# schematic.net
KiCad netlist of a schematic drawn in Altium Designer
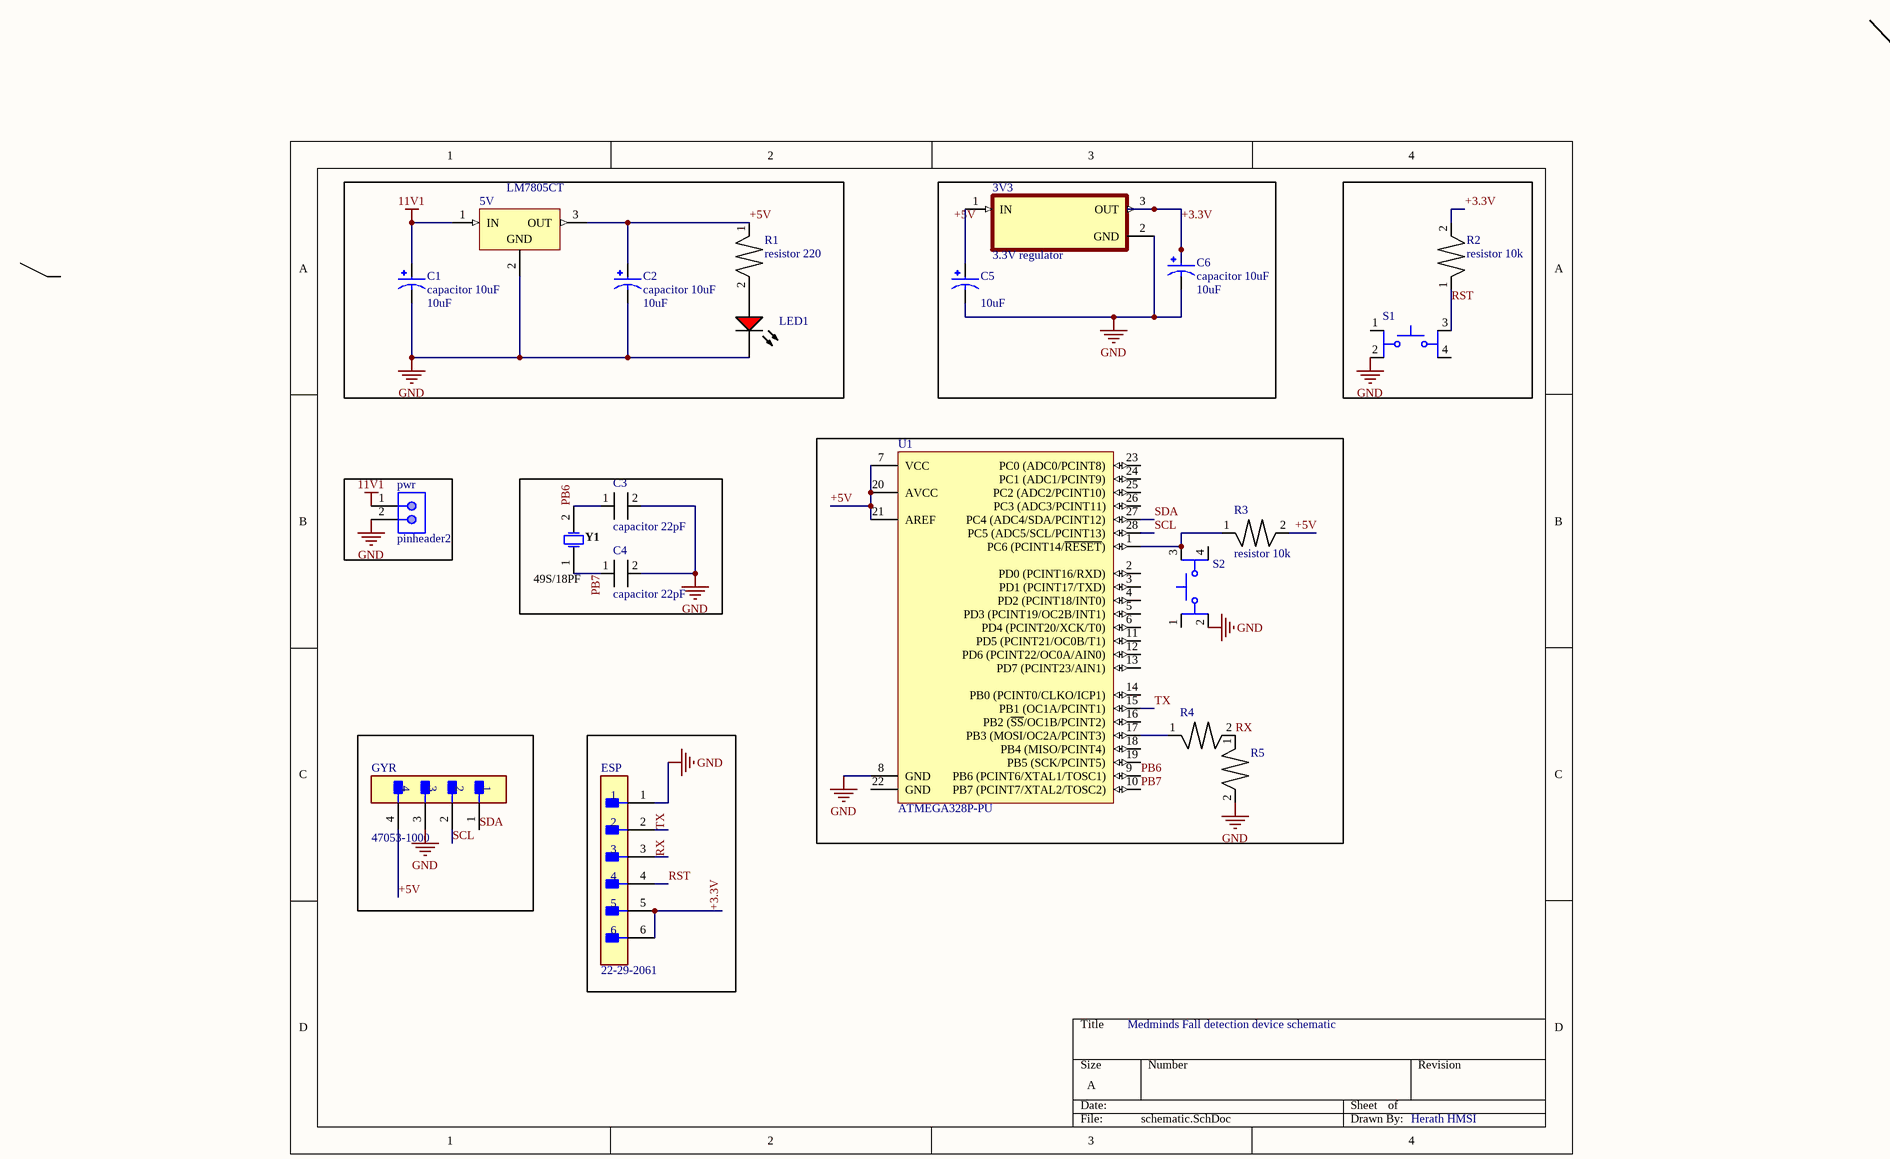
[diagram p0: schematic.SchDoc]

(export (version "E")
  (design (tool "Eeschema 10.0.6"))
  (components
    (comp (ref "3V3")
      (value "3.3V regulator")
      (footprint "3.3V regulator")
      (libsource (lib "schematiclib") (part "3.3V regulator"))
    )
    (comp (ref "5V")
      (value "LM7805CT")
      (footprint "FAIR-TO-220-3")
      (description "Fixed Positive Standard Regulator, 5VBIPolar, PSFM3")
      (libsource (lib "herathhmsi 21") (part "FAIR-LM7805CT-TO220-3"))
    )
    (comp (ref "C1")
      (value "capacitor 10uF")
      (footprint "Capacitor10uF")
      (fields
        (field (name "MANUFACTURER") "Panasonic")
        (field (name "MANUFACTURER PART NUMBER") "ECA-1HM100I")
        (field (name "ALTIUM_VALUE") "10uF")
      )
      (libsource (lib "schematiclib") (part "ECA-1HM100I (2)"))
    )
    (comp (ref "C2")
      (value "capacitor 10uF")
      (footprint "Capacitor10uF")
      (fields
        (field (name "MANUFACTURER") "Panasonic")
        (field (name "MANUFACTURER PART NUMBER") "ECA-1HM100I")
        (field (name "ALTIUM_VALUE") "10uF")
      )
      (libsource (lib "schematiclib") (part "ECA-1HM100I (2)"))
    )
    (comp (ref "C3")
      (value "capacitor 22pF")
      (footprint "Capacitor - duplicate")
      (fields
        (field (name "MANUFACTURER") "Murata")
        (field (name "MANUFACTURER PART NUMBER") "DE21XSA220KN3AX02F")
      )
      (libsource (lib "schematiclib") (part "DE21XSA220KN3AX02F"))
    )
    (comp (ref "C4")
      (value "capacitor 22pF")
      (footprint "Capacitor - duplicate")
      (fields
        (field (name "MANUFACTURER") "Murata")
        (field (name "MANUFACTURER PART NUMBER") "DE21XSA220KN3AX02F")
      )
      (libsource (lib "schematiclib") (part "DE21XSA220KN3AX02F"))
    )
    (comp (ref "C5")
      (value "10uF")
      (footprint "Capacitor10uF")
      (fields
        (field (name "MANUFACTURER") "Panasonic")
        (field (name "MANUFACTURER PART NUMBER") "ECA-1HM100I")
        (field (name "Comment") "capacitor 10uF")
      )
      (libsource (lib "schematiclib") (part "ECA-1HM100I (2)"))
    )
    (comp (ref "C6")
      (value "capacitor 10uF")
      (footprint "Capacitor10uF")
      (fields
        (field (name "MANUFACTURER") "Panasonic")
        (field (name "MANUFACTURER PART NUMBER") "ECA-1HM100I")
        (field (name "ALTIUM_VALUE") "10uF")
      )
      (libsource (lib "schematiclib") (part "ECA-1HM100I (2)"))
    )
    (comp (ref "ESP")
      (value "22-29-2061")
      (footprint "FP-22-29-2061-MFG")
      (libsource (lib "schematiclib") (part "22-29-2061"))
    )
    (comp (ref "GYR")
      (value "47053-1000")
      (footprint "FP-47053-1000-MFG")
      (description "CONN HEADER VERT 4POS 2.54MM")
      (libsource (lib "Altium Content Vault") (part "299a8cea1bdcbc3624fe62c390fa72c"))
    )
    (comp (ref "LED1")
      (value "LED1")
      (footprint "INDPR60-254-520X380X650")
      (description "LED Uni-Color Red, 100 mW, 30 mA, -55 to 100 degC, 2-Pin THD, RoHS, Bulk")
      (fields (field (name "MANUFACTURER") "Lite-On"))
      (libsource (lib "herathhmsi 21") (part "LED-RED-AK-2"))
    )
    (comp (ref "pwr")
      (value "pinheader2")
      (footprint "TECO-5-146280-2_V")
      (libsource (lib "schematiclib") (part "pinheader2"))
    )
    (comp (ref "R1")
      (value "resistor 220")
      (footprint "Axial 0.4")
      (description "Fixed Resistor, Carbon Film, 0.25W, 220ohm, 350V, 5% +/-Tol, -400,0ppm/Cel, Through Hole Mount")
      (fields
        (field (name "MANUFACTURER") "Stackpole Electronics")
        (field (name "MANUFACTURER PART NUMBER") "CF14JT220R")
      )
      (libsource (lib "schematiclib") (part "CF14JT220R"))
    )
    (comp (ref "R2")
      (value "resistor 10k")
      (footprint "Axial 0.4")
      (description "Fixed Resistor, Carbon Film, 0.25W, 10000ohm, 350V, 5% +/-Tol, -500,0ppm/Cel, Through Hole Mount")
      (fields
        (field (name "MANUFACTURER") "Stackpole Electronics")
        (field (name "MANUFACTURER PART NUMBER") "CF14JT10K0")
      )
      (libsource (lib "schematiclib") (part "CF14JT10K0"))
    )
    (comp (ref "R3")
      (value "resistor 10k")
      (footprint "Axial 0.4")
      (description "Fixed Resistor, Carbon Film, 0.25W, 10000ohm, 350V, 5% +/-Tol, -500,0ppm/Cel, Through Hole Mount")
      (fields
        (field (name "MANUFACTURER") "Stackpole Electronics")
        (field (name "MANUFACTURER PART NUMBER") "CF14JT10K0")
      )
      (libsource (lib "schematiclib") (part "CF14JT10K0"))
    )
    (comp (ref "R4")
      (value "resistor1k")
      (footprint "Axial 0.4")
      (description "Fixed Resistor, Carbon Film, 0.25W, 1000ohm, 350V, 5% +/-Tol, -400,0ppm/Cel, Through Hole Mount")
      (fields
        (field (name "MANUFACTURER") "Stackpole Electronics")
        (field (name "MANUFACTURER PART NUMBER") "CF14JT1K00")
      )
      (libsource (lib "schematiclib") (part "CF14JT1K00"))
    )
    (comp (ref "R5")
      (value "resistor 2k")
      (footprint "Axial 0.4")
      (description "Res Carbon Film 2K Ohm 5% 1/4W -400ppm/°C to 0ppm/°C Conformal AXL Thru-Hole T/R")
      (fields
        (field (name "MANUFACTURER") "Stackpole Electronics")
        (field (name "MANUFACTURER PART NUMBER") "CF14JT2K00")
      )
      (libsource (lib "schematiclib") (part "CF14JT2K00"))
    )
    (comp (ref "S1")
      (value "tacktile switch")
      (footprint "SW_TL1105AF160Q")
      (fields
        (field (name "MANUFACTURER") "E-Switch")
        (field (name "MANUFACTURER PART NUMBER") "TL1105AF160Q")
      )
      (libsource (lib "schematiclib") (part "TL1105AF160Q"))
    )
    (comp (ref "S2")
      (value "tacktile switch")
      (footprint "SW_TL1105AF160Q")
      (fields
        (field (name "MANUFACTURER") "E-Switch")
        (field (name "MANUFACTURER PART NUMBER") "TL1105AF160Q")
      )
      (libsource (lib "") (part "TL1105AF160Q_1"))
    )
    (comp (ref "U1")
      (value "ATMEGA328P-PU")
      (footprint "ATML-28P3")
      (fields (field (name "MANUFACTURER") "Atmel"))
      (libsource (lib "herathhmsi 21") (part "MC-8B-ATM48-IL28"))
    )
    (comp (ref "Y1")
      (value "49S/18PF")
      (footprint "JPY-49S-18PF")
      (description "Crystal, 16 MHz, +/-20 ppm, 18 pF, -20 to 70 degC, 2-Pin THD, RoHS")
      (fields (field (name "MANUFACTURER") "Shenzhen Jingpengyuan"))
      (libsource (lib "herathhmsi 21") (part "XTAL-1-2-2"))
    )
  )
  (nets
    (net (code "1") (name "/+3.3V") (class "Default")
      (node (ref "3V3") (pin "3") (pinfunction "OUT_3") (pintype "output"))
      (node (ref "C6") (pin "P") (pinfunction "P_P") (pintype "passive"))
      (node (ref "ESP") (pin "5") (pinfunction "5_5") (pintype "passive"))
      (node (ref "ESP") (pin "6") (pinfunction "6_6") (pintype "passive"))
      (node (ref "R2") (pin "2") (pinfunction "2_2") (pintype "passive"))
    )
    (net (code "2") (name "/+5V") (class "Default")
      (node (ref "3V3") (pin "1") (pinfunction "IN_1") (pintype "input"))
      (node (ref "5V") (pin "3") (pinfunction "OUT_3") (pintype "output"))
      (node (ref "C2") (pin "P") (pinfunction "P_P") (pintype "passive"))
      (node (ref "C5") (pin "P") (pinfunction "P_P") (pintype "passive"))
      (node (ref "GYR") (pin "4") (pinfunction "4_4") (pintype "passive"))
      (node (ref "R1") (pin "1") (pinfunction "1_1") (pintype "passive"))
      (node (ref "R3") (pin "2") (pinfunction "2_2") (pintype "passive"))
      (node (ref "U1") (pin "20") (pinfunction "AVCC_20") (pintype "power_in"))
      (node (ref "U1") (pin "21") (pinfunction "AREF_21") (pintype "power_in"))
      (node (ref "U1") (pin "7") (pinfunction "VCC_7") (pintype "power_in"))
    )
    (net (code "3") (name "/PB6") (class "Default")
      (node (ref "C3") (pin "1") (pinfunction "1_1") (pintype "passive"))
      (node (ref "U1") (pin "9") (pinfunction "PB6_(PCINT6/XTAL1/TOSC1)_9") (pintype "bidirectional"))
      (node (ref "Y1") (pin "2") (pinfunction "2_2") (pintype "passive"))
    )
    (net (code "4") (name "/PB7") (class "Default")
      (node (ref "C4") (pin "1") (pinfunction "1_1") (pintype "passive"))
      (node (ref "U1") (pin "10") (pinfunction "PB7_(PCINT7/XTAL2/TOSC2)_10") (pintype "bidirectional"))
      (node (ref "Y1") (pin "1") (pinfunction "1_1") (pintype "passive"))
    )
    (net (code "5") (name "/RST") (class "Default")
      (node (ref "ESP") (pin "4") (pinfunction "4_4") (pintype "passive"))
      (node (ref "R2") (pin "1") (pinfunction "1_1") (pintype "passive"))
      (node (ref "S1") (pin "3") (pinfunction "3_3") (pintype "passive"))
    )
    (net (code "6") (name "/RX") (class "Default")
      (node (ref "ESP") (pin "3") (pinfunction "3_3") (pintype "passive"))
      (node (ref "R4") (pin "2") (pinfunction "2_2") (pintype "passive"))
      (node (ref "R5") (pin "1") (pinfunction "1_1") (pintype "passive"))
    )
    (net (code "7") (name "/SCL") (class "Default")
      (node (ref "GYR") (pin "2") (pinfunction "2_2") (pintype "passive"))
      (node (ref "U1") (pin "28") (pinfunction "PC5_(ADC5/SCL/PCINT13)_28") (pintype "bidirectional"))
    )
    (net (code "8") (name "/SDA") (class "Default")
      (node (ref "GYR") (pin "1") (pinfunction "1_1") (pintype "passive"))
      (node (ref "U1") (pin "27") (pinfunction "PC4_(ADC4/SDA/PCINT12)_27") (pintype "bidirectional"))
    )
    (net (code "9") (name "/TX") (class "Default")
      (node (ref "ESP") (pin "2") (pinfunction "2_2") (pintype "passive"))
      (node (ref "U1") (pin "15") (pinfunction "PB1_(OC1A/PCINT1)_15") (pintype "bidirectional"))
    )
    (net (code "10") (name "11V1") (class "Default")
      (node (ref "5V") (pin "1") (pinfunction "IN_1") (pintype "input"))
      (node (ref "C1") (pin "P") (pinfunction "P_P") (pintype "passive"))
      (node (ref "pwr") (pin "1") (pinfunction "1_1") (pintype "passive"))
    )
    (net (code "11") (name "GND") (class "Default")
      (node (ref "3V3") (pin "2") (pinfunction "GND_2") (pintype "power_in"))
      (node (ref "5V") (pin "2") (pinfunction "GND_2") (pintype "power_in"))
      (node (ref "C1") (pin "N") (pinfunction "N_N") (pintype "passive"))
      (node (ref "C2") (pin "N") (pinfunction "N_N") (pintype "passive"))
      (node (ref "C3") (pin "2") (pinfunction "2_2") (pintype "passive"))
      (node (ref "C4") (pin "2") (pinfunction "2_2") (pintype "passive"))
      (node (ref "C5") (pin "N") (pinfunction "N_N") (pintype "passive"))
      (node (ref "C6") (pin "N") (pinfunction "N_N") (pintype "passive"))
      (node (ref "ESP") (pin "1") (pinfunction "1_1") (pintype "passive"))
      (node (ref "GYR") (pin "3") (pinfunction "3_3") (pintype "passive"))
      (node (ref "LED1") (pin "2") (pinfunction "K_2") (pintype "passive"))
      (node (ref "R5") (pin "2") (pinfunction "2_2") (pintype "passive"))
      (node (ref "S1") (pin "2") (pinfunction "2_2") (pintype "passive"))
      (node (ref "S2") (pin "2") (pinfunction "2_2") (pintype "passive"))
      (node (ref "U1") (pin "8") (pinfunction "GND_8") (pintype "power_in"))
      (node (ref "pwr") (pin "2") (pinfunction "2_2") (pintype "passive"))
    )
    (net (code "12") (name "Net-(LED1-A)") (class "Default")
      (node (ref "LED1") (pin "1") (pinfunction "A_1") (pintype "passive"))
      (node (ref "R1") (pin "2") (pinfunction "2_2") (pintype "passive"))
    )
    (net (code "13") (name "Net-(U1-PB3_(MOSI{slash}OC2A{slash}PCINT3))") (class "Default")
      (node (ref "R4") (pin "1") (pinfunction "1_1") (pintype "passive"))
      (node (ref "U1") (pin "17") (pinfunction "PB3_(MOSI/OC2A/PCINT3)_17") (pintype "bidirectional"))
    )
    (net (code "14") (name "Net-(U1-PC6_(PCINT14{slash}~{RESET}))") (class "Default")
      (node (ref "R3") (pin "1") (pinfunction "1_1") (pintype "passive"))
      (node (ref "S2") (pin "3") (pinfunction "3_3") (pintype "passive"))
      (node (ref "U1") (pin "1") (pinfunction "PC6_(PCINT14/~{RESET})_1") (pintype "bidirectional"))
    )
    (net (code "15") (name "unconnected-(S1-Pad1)") (class "Default")
      (node (ref "S1") (pin "1") (pinfunction "1_1") (pintype "passive"))
    )
    (net (code "16") (name "unconnected-(S1-Pad4)") (class "Default")
      (node (ref "S1") (pin "4") (pinfunction "4_4") (pintype "passive"))
    )
    (net (code "17") (name "unconnected-(S2-Pad1)") (class "Default")
      (node (ref "S2") (pin "1") (pinfunction "1_1") (pintype "passive"))
    )
    (net (code "18") (name "unconnected-(S2-Pad4)") (class "Default")
      (node (ref "S2") (pin "4") (pinfunction "4_4") (pintype "passive"))
    )
    (net (code "19") (name "unconnected-(U1-GND-Pad22)") (class "Default")
      (node (ref "U1") (pin "22") (pinfunction "GND_22") (pintype "power_in"))
    )
    (net (code "20") (name "unconnected-(U1-PB0_(PCINT0{slash}CLKO{slash}ICP1)-Pad14)") (class "Default")
      (node (ref "U1") (pin "14") (pinfunction "PB0_(PCINT0/CLKO/ICP1)_14") (pintype "bidirectional"))
    )
    (net (code "21") (name "unconnected-(U1-PB2_(~{SS}{slash}OC1B{slash}PCINT2)-Pad16)") (class "Default")
      (node (ref "U1") (pin "16") (pinfunction "PB2_(~{SS}/OC1B/PCINT2)_16") (pintype "bidirectional"))
    )
    (net (code "22") (name "unconnected-(U1-PB4_(MISO{slash}PCINT4)-Pad18)") (class "Default")
      (node (ref "U1") (pin "18") (pinfunction "PB4_(MISO/PCINT4)_18") (pintype "bidirectional"))
    )
    (net (code "23") (name "unconnected-(U1-PB5_(SCK{slash}PCINT5)-Pad19)") (class "Default")
      (node (ref "U1") (pin "19") (pinfunction "PB5_(SCK/PCINT5)_19") (pintype "bidirectional"))
    )
    (net (code "24") (name "unconnected-(U1-PC0_(ADC0{slash}PCINT8)-Pad23)") (class "Default")
      (node (ref "U1") (pin "23") (pinfunction "PC0_(ADC0/PCINT8)_23") (pintype "bidirectional"))
    )
    (net (code "25") (name "unconnected-(U1-PC1_(ADC1{slash}PCINT9)-Pad24)") (class "Default")
      (node (ref "U1") (pin "24") (pinfunction "PC1_(ADC1/PCINT9)_24") (pintype "bidirectional"))
    )
    (net (code "26") (name "unconnected-(U1-PC2_(ADC2{slash}PCINT10)-Pad25)") (class "Default")
      (node (ref "U1") (pin "25") (pinfunction "PC2_(ADC2/PCINT10)_25") (pintype "bidirectional"))
    )
    (net (code "27") (name "unconnected-(U1-PC3_(ADC3{slash}PCINT11)-Pad26)") (class "Default")
      (node (ref "U1") (pin "26") (pinfunction "PC3_(ADC3/PCINT11)_26") (pintype "bidirectional"))
    )
    (net (code "28") (name "unconnected-(U1-PD0_(PCINT16{slash}RXD)-Pad2)") (class "Default")
      (node (ref "U1") (pin "2") (pinfunction "PD0_(PCINT16/RXD)_2") (pintype "bidirectional"))
    )
    (net (code "29") (name "unconnected-(U1-PD1_(PCINT17{slash}TXD)-Pad3)") (class "Default")
      (node (ref "U1") (pin "3") (pinfunction "PD1_(PCINT17/TXD)_3") (pintype "bidirectional"))
    )
    (net (code "30") (name "unconnected-(U1-PD2_(PCINT18{slash}INT0)-Pad4)") (class "Default")
      (node (ref "U1") (pin "4") (pinfunction "PD2_(PCINT18/INT0)_4") (pintype "bidirectional"))
    )
    (net (code "31") (name "unconnected-(U1-PD3_(PCINT19{slash}OC2B{slash}INT1)-Pad5)") (class "Default")
      (node (ref "U1") (pin "5") (pinfunction "PD3_(PCINT19/OC2B/INT1)_5") (pintype "bidirectional"))
    )
    (net (code "32") (name "unconnected-(U1-PD4_(PCINT20{slash}XCK{slash}T0)-Pad6)") (class "Default")
      (node (ref "U1") (pin "6") (pinfunction "PD4_(PCINT20/XCK/T0)_6") (pintype "bidirectional"))
    )
    (net (code "33") (name "unconnected-(U1-PD5_(PCINT21{slash}OC0B{slash}T1)-Pad11)") (class "Default")
      (node (ref "U1") (pin "11") (pinfunction "PD5_(PCINT21/OC0B/T1)_11") (pintype "bidirectional"))
    )
    (net (code "34") (name "unconnected-(U1-PD6_(PCINT22{slash}OC0A{slash}AIN0)-Pad12)") (class "Default")
      (node (ref "U1") (pin "12") (pinfunction "PD6_(PCINT22/OC0A/AIN0)_12") (pintype "bidirectional"))
    )
    (net (code "35") (name "unconnected-(U1-PD7_(PCINT23{slash}AIN1)-Pad13)") (class "Default")
      (node (ref "U1") (pin "13") (pinfunction "PD7_(PCINT23/AIN1)_13") (pintype "bidirectional"))
    )
  )
)
